# EEZ_DIB_BP3C_r2B2.net
KiCad netlist of a schematic drawn in EAGLE
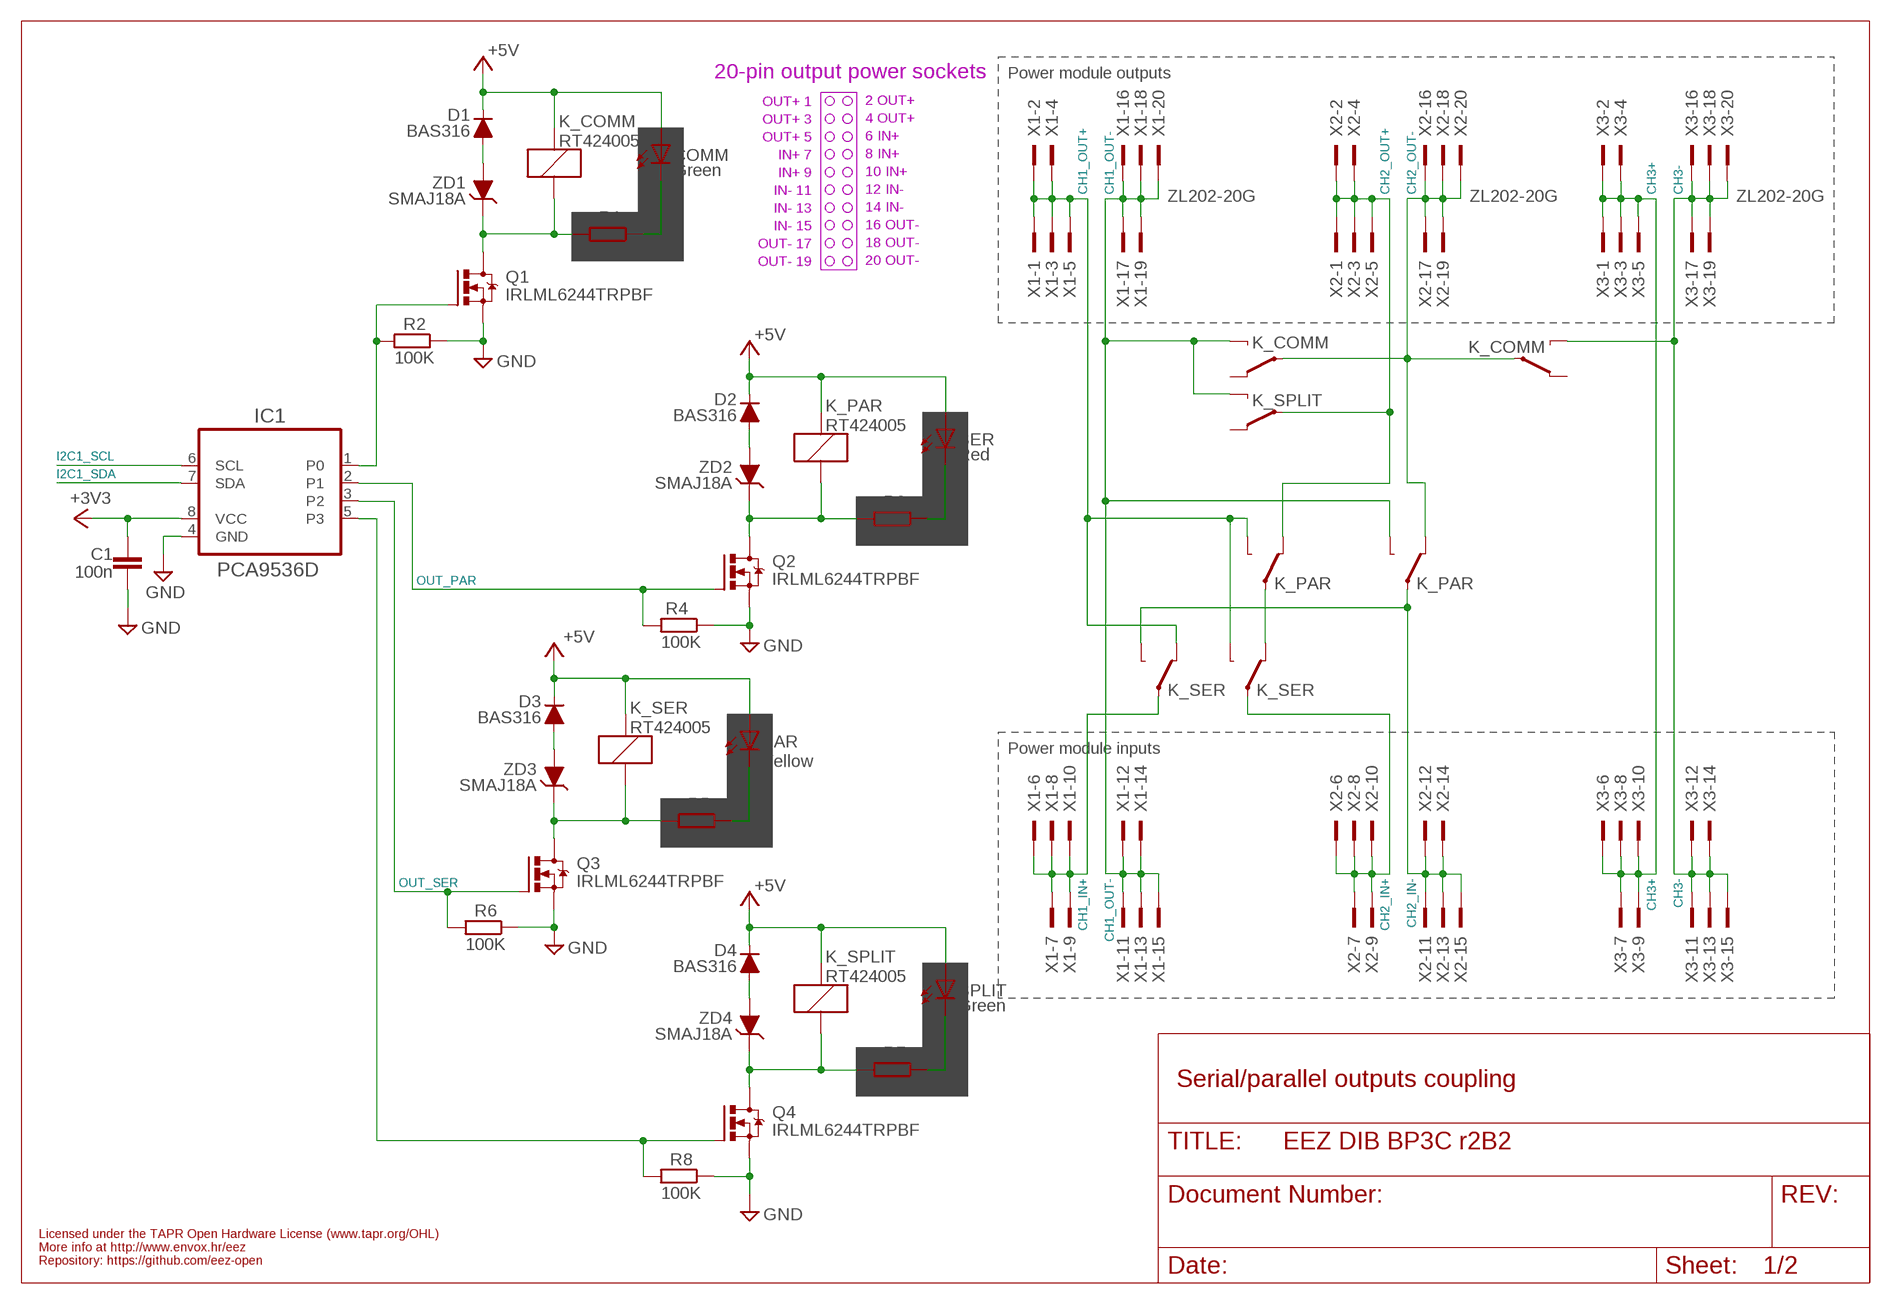
[diagram p0: schematic, sheet 1]
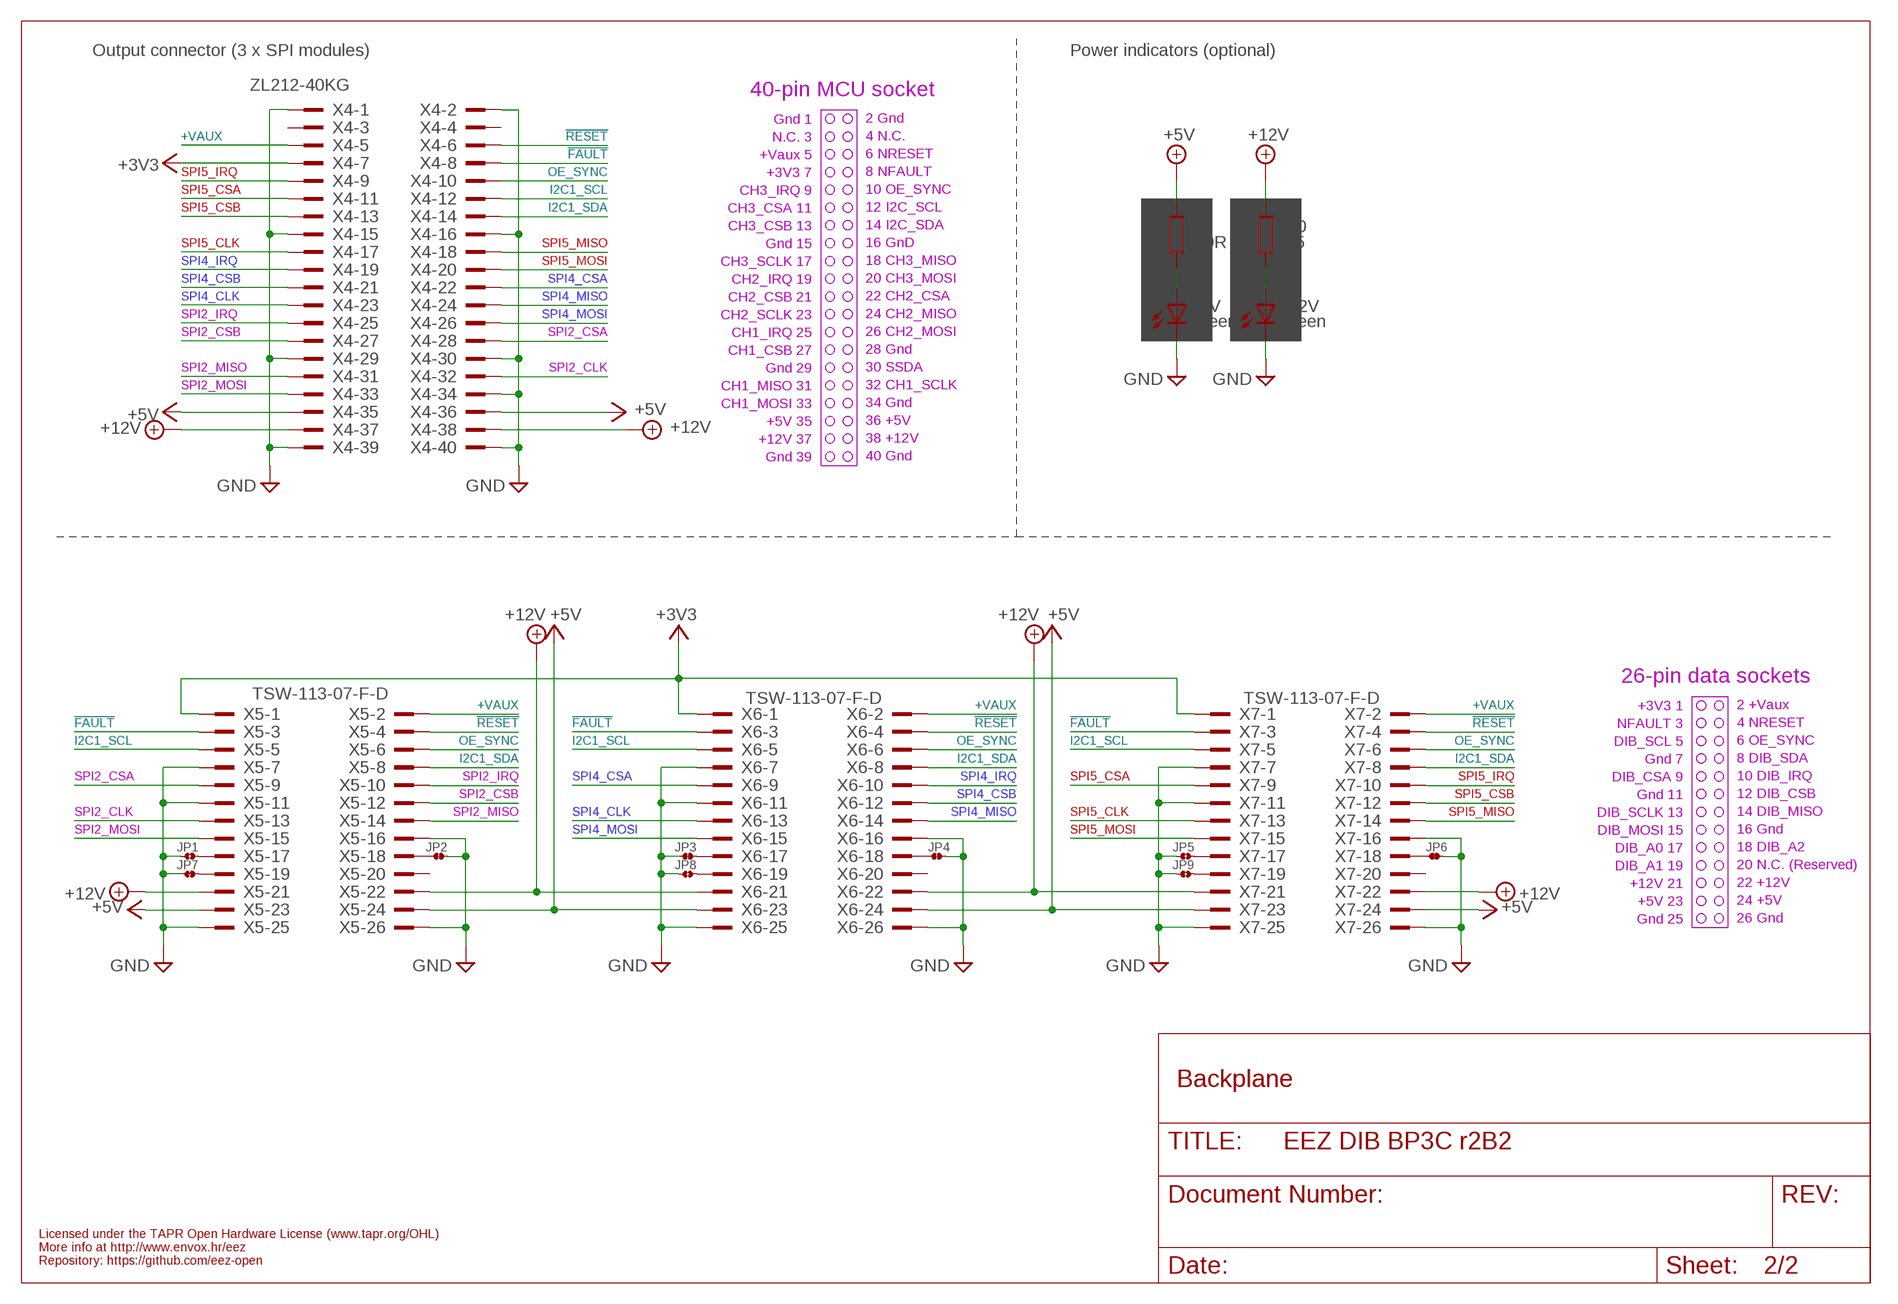
[diagram p1: schematic, sheet 2]

(export (version "E")
  (design (tool "Eeschema 10.0.6"))
  (components
    (comp (ref "C1")
      (value "100n")
      (footprint "eagle-import:C0603")
      (libsource (lib "eagle-import") (part "C-EUC0603"))
    )
    (comp (ref "COMM")
      (value "Green")
      (footprint "eagle-import:LED_0805")
      (libsource (lib "eagle-import") (part "LED0805"))
    )
    (comp (ref "D1")
      (value "BAS316")
      (footprint "eagle-import:SOD323-R")
      (libsource (lib "eagle-import") (part "DIODESOD323R"))
    )
    (comp (ref "D2")
      (value "BAS316")
      (footprint "eagle-import:SOD323-R")
      (libsource (lib "eagle-import") (part "DIODESOD323R"))
    )
    (comp (ref "D3")
      (value "BAS316")
      (footprint "eagle-import:SOD323-R")
      (libsource (lib "eagle-import") (part "DIODESOD323R"))
    )
    (comp (ref "D4")
      (value "BAS316")
      (footprint "eagle-import:SOD323-R")
      (libsource (lib "eagle-import") (part "DIODESOD323R"))
    )
    (comp (ref "IC1")
      (value "PCA9536D")
      (footprint "eagle-import:SOIC127P600X173-8N")
      (libsource (lib "eagle-import") (part "PCA9536D"))
    )
    (comp (ref "K_COMM")
      (value "RT424005")
      (footprint "eagle-import:RT-C_016A5_ROUND")
      (libsource (lib "eagle-import") (part "RELAY_RT314012-2"))
    )
    (comp (ref "K_PAR")
      (value "RT424005")
      (footprint "eagle-import:RT-C_016A5_ROUND")
      (libsource (lib "eagle-import") (part "RELAY_RT314012-2"))
    )
    (comp (ref "K_SER")
      (value "RT424005")
      (footprint "eagle-import:RT-C_016A5_ROUND")
      (libsource (lib "eagle-import") (part "RELAY_RT314012-2"))
    )
    (comp (ref "K_SPLIT")
      (value "RT424005")
      (footprint "eagle-import:RT-C_016A5_ROUND")
      (libsource (lib "eagle-import") (part "RELAY_RT314012-2"))
    )
    (comp (ref "PAR")
      (value "Yellow")
      (footprint "eagle-import:LED_0805")
      (libsource (lib "eagle-import") (part "LED0805"))
    )
    (comp (ref "Q1")
      (value "IRLML6244TRPBF")
      (footprint "eagle-import:SOT103P240X110-3N")
      (fields
        (field (name "MPN") "2N7002-7-F")
        (field (name "MPN_1") "2N7002-7-F")
        (field (name "OC_FARNELL") "1713823")
        (field (name "OC_NEWARK") "25R5679")
        (field (name "PACKAGE") "SOT-23-3")
        (field (name "SUPPLIER") "DIODES INC.")
      )
      (libsource (lib "eagle-import") (part "2N7002"))
    )
    (comp (ref "Q2")
      (value "IRLML6244TRPBF")
      (footprint "eagle-import:SOT103P240X110-3N")
      (fields
        (field (name "MPN") "2N7002-7-F")
        (field (name "MPN_1") "2N7002-7-F")
        (field (name "OC_FARNELL") "1713823")
        (field (name "OC_NEWARK") "25R5679")
        (field (name "PACKAGE") "SOT-23-3")
        (field (name "SUPPLIER") "DIODES INC.")
      )
      (libsource (lib "eagle-import") (part "2N7002"))
    )
    (comp (ref "Q3")
      (value "IRLML6244TRPBF")
      (footprint "eagle-import:SOT103P240X110-3N")
      (fields
        (field (name "MPN") "2N7002-7-F")
        (field (name "MPN_1") "2N7002-7-F")
        (field (name "OC_FARNELL") "1713823")
        (field (name "OC_NEWARK") "25R5679")
        (field (name "PACKAGE") "SOT-23-3")
        (field (name "SUPPLIER") "DIODES INC.")
      )
      (libsource (lib "eagle-import") (part "2N7002"))
    )
    (comp (ref "Q4")
      (value "IRLML6244TRPBF")
      (footprint "eagle-import:SOT103P240X110-3N")
      (fields
        (field (name "MPN") "2N7002-7-F")
        (field (name "MPN_1") "2N7002-7-F")
        (field (name "OC_FARNELL") "1713823")
        (field (name "OC_NEWARK") "25R5679")
        (field (name "PACKAGE") "SOT-23-3")
        (field (name "SUPPLIER") "DIODES INC.")
      )
      (libsource (lib "eagle-import") (part "2N7002"))
    )
    (comp (ref "R1")
      (value "330R")
      (footprint "eagle-import:R0805")
      (libsource (lib "eagle-import") (part "R-EU_R0805"))
    )
    (comp (ref "R2")
      (value "100K")
      (footprint "eagle-import:R0805")
      (libsource (lib "eagle-import") (part "R-EU_R0805"))
    )
    (comp (ref "R3")
      (value "330R")
      (footprint "eagle-import:R0805")
      (libsource (lib "eagle-import") (part "R-EU_R0805"))
    )
    (comp (ref "R4")
      (value "100K")
      (footprint "eagle-import:R0805")
      (libsource (lib "eagle-import") (part "R-EU_R0805"))
    )
    (comp (ref "R5")
      (value "330R")
      (footprint "eagle-import:R0805")
      (libsource (lib "eagle-import") (part "R-EU_R0805"))
    )
    (comp (ref "R6")
      (value "100K")
      (footprint "eagle-import:R0805")
      (libsource (lib "eagle-import") (part "R-EU_R0805"))
    )
    (comp (ref "R7")
      (value "330R")
      (footprint "eagle-import:R0805")
      (libsource (lib "eagle-import") (part "R-EU_R0805"))
    )
    (comp (ref "R8")
      (value "100K")
      (footprint "eagle-import:R0805")
      (libsource (lib "eagle-import") (part "R-EU_R0805"))
    )
    (comp (ref "SER")
      (value "Red")
      (footprint "eagle-import:LED_0805")
      (libsource (lib "eagle-import") (part "LED0805"))
    )
    (comp (ref "SPLIT")
      (value "Green")
      (footprint "eagle-import:LED_0805")
      (libsource (lib "eagle-import") (part "LED0805"))
    )
    (comp (ref "X1")
      (value "ZL202-20G")
      (footprint "eagle-import:DS1021-2_10SF11")
      (libsource (lib "eagle-import") (part "DS1021-210SF11"))
    )
    (comp (ref "X2")
      (value "ZL202-20G")
      (footprint "eagle-import:DS1021-2_10SF11")
      (libsource (lib "eagle-import") (part "DS1021-210SF11"))
    )
    (comp (ref "X3")
      (value "ZL202-20G")
      (footprint "eagle-import:DS1021-2_10SF11")
      (libsource (lib "eagle-import") (part "DS1021-210SF11"))
    )
    (comp (ref "ZD1")
      (value "SMAJ18A")
      (footprint "eagle-import:DO214AC")
      (libsource (lib "eagle-import") (part "PSMAXX"))
    )
    (comp (ref "ZD2")
      (value "SMAJ18A")
      (footprint "eagle-import:DO214AC")
      (libsource (lib "eagle-import") (part "PSMAXX"))
    )
    (comp (ref "ZD3")
      (value "SMAJ18A")
      (footprint "eagle-import:DO214AC")
      (libsource (lib "eagle-import") (part "PSMAXX"))
    )
    (comp (ref "ZD4")
      (value "SMAJ18A")
      (footprint "eagle-import:DO214AC")
      (libsource (lib "eagle-import") (part "PSMAXX"))
    )
    (comp (ref "+5V")
      (value "Green")
      (footprint "eagle-import:LED_0805")
      (libsource (lib "eagle-import") (part "LED0805"))
    )
    (comp (ref "+12V")
      (value "Green")
      (footprint "eagle-import:LED_0805")
      (libsource (lib "eagle-import") (part "LED0805"))
    )
    (comp (ref "JP1")
      (value "JP2-CUT")
      (footprint "eagle-import:JP2-CUT")
      (libsource (lib "eagle-import") (part "JP2-CUT"))
    )
    (comp (ref "JP2")
      (value "JP2-NOCUT")
      (footprint "eagle-import:JP2-NOCUT")
      (libsource (lib "eagle-import") (part "JP2-NOCUT"))
    )
    (comp (ref "JP3")
      (value "JP2-NOCUT")
      (footprint "eagle-import:JP2-NOCUT")
      (libsource (lib "eagle-import") (part "JP2-NOCUT"))
    )
    (comp (ref "JP4")
      (value "JP2-NOCUT")
      (footprint "eagle-import:JP2-NOCUT")
      (libsource (lib "eagle-import") (part "JP2-NOCUT"))
    )
    (comp (ref "JP5")
      (value "JP2-CUT")
      (footprint "eagle-import:JP2-CUT")
      (libsource (lib "eagle-import") (part "JP2-CUT"))
    )
    (comp (ref "JP6")
      (value "JP2-NOCUT")
      (footprint "eagle-import:JP2-NOCUT")
      (libsource (lib "eagle-import") (part "JP2-NOCUT"))
    )
    (comp (ref "JP7")
      (value "JP2-NOCUT")
      (footprint "eagle-import:JP2-NOCUT")
      (libsource (lib "eagle-import") (part "JP2-NOCUT"))
    )
    (comp (ref "JP8")
      (value "JP2-CUT")
      (footprint "eagle-import:JP2-CUT")
      (libsource (lib "eagle-import") (part "JP2-CUT"))
    )
    (comp (ref "JP9")
      (value "JP2-CUT")
      (footprint "eagle-import:JP2-CUT")
      (libsource (lib "eagle-import") (part "JP2-CUT"))
    )
    (comp (ref "R9")
      (value "470R")
      (footprint "eagle-import:R0805")
      (libsource (lib "eagle-import") (part "R-EU_R0805"))
    )
    (comp (ref "R10")
      (value "1K5")
      (footprint "eagle-import:R0805")
      (libsource (lib "eagle-import") (part "R-EU_R0805"))
    )
    (comp (ref "X4")
      (value "ZL212-40KG")
      (footprint "eagle-import:ZL212-40KG")
      (libsource (lib "eagle-import") (part "ZL212-40KG"))
    )
    (comp (ref "X5")
      (value "TSW-113-07-F-D")
      (footprint "eagle-import:TSW-113-07-F-D")
      (libsource (lib "eagle-import") (part "TSW-113-07-F-D"))
    )
    (comp (ref "X6")
      (value "TSW-113-07-F-D")
      (footprint "eagle-import:TSW-113-07-F-D")
      (libsource (lib "eagle-import") (part "TSW-113-07-F-D"))
    )
    (comp (ref "X7")
      (value "TSW-113-07-F-D")
      (footprint "eagle-import:TSW-113-07-F-D")
      (libsource (lib "eagle-import") (part "TSW-113-07-F-D"))
    )
  )
  (nets
    (net (code "1") (name "+3V3") (class "Default")
      (node (ref "C1") (pin "1") (pinfunction "1_1") (pintype "passive"))
      (node (ref "IC1") (pin "8") (pinfunction "VCC_8") (pintype "passive"))
      (node (ref "X4") (pin "7") (pinfunction "1_7") (pintype "passive"))
      (node (ref "X5") (pin "1") (pinfunction "1_1") (pintype "passive"))
      (node (ref "X6") (pin "1") (pinfunction "1_1") (pintype "passive"))
      (node (ref "X7") (pin "1") (pinfunction "1_1") (pintype "passive"))
    )
    (net (code "2") (name "+5V") (class "Default")
      (node (ref "COMM") (pin "A") (pinfunction "A_A") (pintype "passive"))
      (node (ref "D1") (pin "C") (pinfunction "C_C") (pintype "passive"))
      (node (ref "D2") (pin "C") (pinfunction "C_C") (pintype "passive"))
      (node (ref "D3") (pin "C") (pinfunction "C_C") (pintype "passive"))
      (node (ref "D4") (pin "C") (pinfunction "C_C") (pintype "passive"))
      (node (ref "K_COMM") (pin "A2") (pinfunction "C1_A2") (pintype "passive"))
      (node (ref "K_PAR") (pin "A2") (pinfunction "C1_A2") (pintype "passive"))
      (node (ref "K_SER") (pin "A2") (pinfunction "C1_A2") (pintype "passive"))
      (node (ref "K_SPLIT") (pin "A2") (pinfunction "C1_A2") (pintype "passive"))
      (node (ref "PAR") (pin "A") (pinfunction "A_A") (pintype "passive"))
      (node (ref "R9") (pin "1") (pinfunction "1_1") (pintype "passive"))
      (node (ref "SER") (pin "A") (pinfunction "A_A") (pintype "passive"))
      (node (ref "SPLIT") (pin "A") (pinfunction "A_A") (pintype "passive"))
      (node (ref "X4") (pin "35") (pinfunction "1_35") (pintype "passive"))
      (node (ref "X4") (pin "36") (pinfunction "1_36") (pintype "passive"))
      (node (ref "X5") (pin "23") (pinfunction "1_23") (pintype "passive"))
      (node (ref "X5") (pin "24") (pinfunction "1_24") (pintype "passive"))
      (node (ref "X6") (pin "23") (pinfunction "1_23") (pintype "passive"))
      (node (ref "X6") (pin "24") (pinfunction "1_24") (pintype "passive"))
      (node (ref "X7") (pin "23") (pinfunction "1_23") (pintype "passive"))
      (node (ref "X7") (pin "24") (pinfunction "1_24") (pintype "passive"))
    )
    (net (code "3") (name "+12V") (class "Default")
      (node (ref "R10") (pin "1") (pinfunction "1_1") (pintype "passive"))
      (node (ref "X4") (pin "37") (pinfunction "1_37") (pintype "passive"))
      (node (ref "X4") (pin "38") (pinfunction "1_38") (pintype "passive"))
      (node (ref "X5") (pin "21") (pinfunction "1_21") (pintype "passive"))
      (node (ref "X5") (pin "22") (pinfunction "1_22") (pintype "passive"))
      (node (ref "X6") (pin "21") (pinfunction "1_21") (pintype "passive"))
      (node (ref "X6") (pin "22") (pinfunction "1_22") (pintype "passive"))
      (node (ref "X7") (pin "21") (pinfunction "1_21") (pintype "passive"))
      (node (ref "X7") (pin "22") (pinfunction "1_22") (pintype "passive"))
    )
    (net (code "4") (name "+VAUX") (class "Default")
      (node (ref "X4") (pin "5") (pinfunction "1_5") (pintype "passive"))
      (node (ref "X5") (pin "2") (pinfunction "1_2") (pintype "passive"))
      (node (ref "X6") (pin "2") (pinfunction "1_2") (pintype "passive"))
      (node (ref "X7") (pin "2") (pinfunction "1_2") (pintype "passive"))
    )
    (net (code "5") (name "CH1_IN+") (class "Default")
      (node (ref "K_SER") (pin "11A") (pinfunction "P_11A") (pintype "passive"))
      (node (ref "X1") (pin "10") (pinfunction "1_10") (pintype "passive"))
      (node (ref "X1") (pin "6") (pinfunction "1_6") (pintype "passive"))
      (node (ref "X1") (pin "7") (pinfunction "1_7") (pintype "passive"))
      (node (ref "X1") (pin "8") (pinfunction "1_8") (pintype "passive"))
      (node (ref "X1") (pin "9") (pinfunction "1_9") (pintype "passive"))
    )
    (net (code "6") (name "CH1_OUT+") (class "Default")
      (node (ref "K_PAR") (pin "14A") (pinfunction "O_14A") (pintype "passive"))
      (node (ref "K_SER") (pin "12A") (pinfunction "S_12A") (pintype "passive"))
      (node (ref "K_SER") (pin "14B") (pinfunction "O_14B") (pintype "passive"))
      (node (ref "X1") (pin "1") (pinfunction "1_1") (pintype "passive"))
      (node (ref "X1") (pin "2") (pinfunction "1_2") (pintype "passive"))
      (node (ref "X1") (pin "3") (pinfunction "1_3") (pintype "passive"))
      (node (ref "X1") (pin "4") (pinfunction "1_4") (pintype "passive"))
      (node (ref "X1") (pin "5") (pinfunction "1_5") (pintype "passive"))
    )
    (net (code "7") (name "CH1_OUT-") (class "Default")
      (node (ref "K_COMM") (pin "14A") (pinfunction "O_14A") (pintype "passive"))
      (node (ref "K_PAR") (pin "14B") (pinfunction "O_14B") (pintype "passive"))
      (node (ref "K_SPLIT") (pin "14A") (pinfunction "O_14A") (pintype "passive"))
      (node (ref "X1") (pin "11") (pinfunction "1_11") (pintype "passive"))
      (node (ref "X1") (pin "12") (pinfunction "1_12") (pintype "passive"))
      (node (ref "X1") (pin "13") (pinfunction "1_13") (pintype "passive"))
      (node (ref "X1") (pin "14") (pinfunction "1_14") (pintype "passive"))
      (node (ref "X1") (pin "15") (pinfunction "1_15") (pintype "passive"))
      (node (ref "X1") (pin "16") (pinfunction "1_16") (pintype "passive"))
      (node (ref "X1") (pin "17") (pinfunction "1_17") (pintype "passive"))
      (node (ref "X1") (pin "18") (pinfunction "1_18") (pintype "passive"))
      (node (ref "X1") (pin "19") (pinfunction "1_19") (pintype "passive"))
      (node (ref "X1") (pin "20") (pinfunction "1_20") (pintype "passive"))
    )
    (net (code "8") (name "CH2_IN+") (class "Default")
      (node (ref "K_SER") (pin "11B") (pinfunction "P_11B") (pintype "passive"))
      (node (ref "X2") (pin "10") (pinfunction "1_10") (pintype "passive"))
      (node (ref "X2") (pin "6") (pinfunction "1_6") (pintype "passive"))
      (node (ref "X2") (pin "7") (pinfunction "1_7") (pintype "passive"))
      (node (ref "X2") (pin "8") (pinfunction "1_8") (pintype "passive"))
      (node (ref "X2") (pin "9") (pinfunction "1_9") (pintype "passive"))
    )
    (net (code "9") (name "CH2_IN-") (class "Default")
      (node (ref "K_PAR") (pin "11B") (pinfunction "P_11B") (pintype "passive"))
      (node (ref "K_SER") (pin "14A") (pinfunction "O_14A") (pintype "passive"))
      (node (ref "X2") (pin "11") (pinfunction "1_11") (pintype "passive"))
      (node (ref "X2") (pin "12") (pinfunction "1_12") (pintype "passive"))
      (node (ref "X2") (pin "13") (pinfunction "1_13") (pintype "passive"))
      (node (ref "X2") (pin "14") (pinfunction "1_14") (pintype "passive"))
      (node (ref "X2") (pin "15") (pinfunction "1_15") (pintype "passive"))
    )
    (net (code "10") (name "CH2_OUT+") (class "Default")
      (node (ref "K_PAR") (pin "12A") (pinfunction "S_12A") (pintype "passive"))
      (node (ref "K_SPLIT") (pin "11A") (pinfunction "P_11A") (pintype "passive"))
      (node (ref "X2") (pin "1") (pinfunction "1_1") (pintype "passive"))
      (node (ref "X2") (pin "2") (pinfunction "1_2") (pintype "passive"))
      (node (ref "X2") (pin "3") (pinfunction "1_3") (pintype "passive"))
      (node (ref "X2") (pin "4") (pinfunction "1_4") (pintype "passive"))
      (node (ref "X2") (pin "5") (pinfunction "1_5") (pintype "passive"))
    )
    (net (code "11") (name "CH2_OUT-") (class "Default")
      (node (ref "K_COMM") (pin "11A") (pinfunction "P_11A") (pintype "passive"))
      (node (ref "K_COMM") (pin "11B") (pinfunction "P_11B") (pintype "passive"))
      (node (ref "K_PAR") (pin "12B") (pinfunction "S_12B") (pintype "passive"))
      (node (ref "X2") (pin "16") (pinfunction "1_16") (pintype "passive"))
      (node (ref "X2") (pin "17") (pinfunction "1_17") (pintype "passive"))
      (node (ref "X2") (pin "18") (pinfunction "1_18") (pintype "passive"))
      (node (ref "X2") (pin "19") (pinfunction "1_19") (pintype "passive"))
      (node (ref "X2") (pin "20") (pinfunction "1_20") (pintype "passive"))
    )
    (net (code "12") (name "CH3+") (class "Default")
      (node (ref "X3") (pin "1") (pinfunction "1_1") (pintype "passive"))
      (node (ref "X3") (pin "10") (pinfunction "1_10") (pintype "passive"))
      (node (ref "X3") (pin "2") (pinfunction "1_2") (pintype "passive"))
      (node (ref "X3") (pin "3") (pinfunction "1_3") (pintype "passive"))
      (node (ref "X3") (pin "4") (pinfunction "1_4") (pintype "passive"))
      (node (ref "X3") (pin "5") (pinfunction "1_5") (pintype "passive"))
      (node (ref "X3") (pin "6") (pinfunction "1_6") (pintype "passive"))
      (node (ref "X3") (pin "7") (pinfunction "1_7") (pintype "passive"))
      (node (ref "X3") (pin "8") (pinfunction "1_8") (pintype "passive"))
      (node (ref "X3") (pin "9") (pinfunction "1_9") (pintype "passive"))
    )
    (net (code "13") (name "CH3-") (class "Default")
      (node (ref "K_COMM") (pin "14B") (pinfunction "O_14B") (pintype "passive"))
      (node (ref "X3") (pin "11") (pinfunction "1_11") (pintype "passive"))
      (node (ref "X3") (pin "12") (pinfunction "1_12") (pintype "passive"))
      (node (ref "X3") (pin "13") (pinfunction "1_13") (pintype "passive"))
      (node (ref "X3") (pin "14") (pinfunction "1_14") (pintype "passive"))
      (node (ref "X3") (pin "15") (pinfunction "1_15") (pintype "passive"))
      (node (ref "X3") (pin "16") (pinfunction "1_16") (pintype "passive"))
      (node (ref "X3") (pin "17") (pinfunction "1_17") (pintype "passive"))
      (node (ref "X3") (pin "18") (pinfunction "1_18") (pintype "passive"))
      (node (ref "X3") (pin "19") (pinfunction "1_19") (pintype "passive"))
      (node (ref "X3") (pin "20") (pinfunction "1_20") (pintype "passive"))
    )
    (net (code "14") (name "GND") (class "Default")
      (node (ref "+12V") (pin "C") (pinfunction "C_C") (pintype "passive"))
      (node (ref "+5V") (pin "C") (pinfunction "C_C") (pintype "passive"))
      (node (ref "C1") (pin "2") (pinfunction "2_2") (pintype "passive"))
      (node (ref "IC1") (pin "4") (pinfunction "GND_4") (pintype "passive"))
      (node (ref "JP1") (pin "1") (pinfunction "1_1") (pintype "passive"))
      (node (ref "JP2") (pin "2") (pinfunction "2_2") (pintype "passive"))
      (node (ref "JP3") (pin "1") (pinfunction "1_1") (pintype "passive"))
      (node (ref "JP4") (pin "2") (pinfunction "2_2") (pintype "passive"))
      (node (ref "JP5") (pin "1") (pinfunction "1_1") (pintype "passive"))
      (node (ref "JP6") (pin "2") (pinfunction "2_2") (pintype "passive"))
      (node (ref "JP7") (pin "1") (pinfunction "1_1") (pintype "passive"))
      (node (ref "JP8") (pin "1") (pinfunction "1_1") (pintype "passive"))
      (node (ref "JP9") (pin "1") (pinfunction "1_1") (pintype "passive"))
      (node (ref "Q1") (pin "2") (pinfunction "S_2") (pintype "passive"))
      (node (ref "Q2") (pin "2") (pinfunction "S_2") (pintype "passive"))
      (node (ref "Q3") (pin "2") (pinfunction "S_2") (pintype "passive"))
      (node (ref "Q4") (pin "2") (pinfunction "S_2") (pintype "passive"))
      (node (ref "R2") (pin "1") (pinfunction "1_1") (pintype "passive"))
      (node (ref "R4") (pin "1") (pinfunction "1_1") (pintype "passive"))
      (node (ref "R6") (pin "1") (pinfunction "1_1") (pintype "passive"))
      (node (ref "R8") (pin "1") (pinfunction "1_1") (pintype "passive"))
      (node (ref "X4") (pin "1") (pinfunction "1_1") (pintype "passive"))
      (node (ref "X4") (pin "15") (pinfunction "1_15") (pintype "passive"))
      (node (ref "X4") (pin "16") (pinfunction "1_16") (pintype "passive"))
      (node (ref "X4") (pin "2") (pinfunction "1_2") (pintype "passive"))
      (node (ref "X4") (pin "29") (pinfunction "1_29") (pintype "passive"))
      (node (ref "X4") (pin "30") (pinfunction "1_30") (pintype "passive"))
      (node (ref "X4") (pin "34") (pinfunction "1_34") (pintype "passive"))
      (node (ref "X4") (pin "39") (pinfunction "1_39") (pintype "passive"))
      (node (ref "X4") (pin "40") (pinfunction "1_40") (pintype "passive"))
      (node (ref "X5") (pin "11") (pinfunction "1_11") (pintype "passive"))
      (node (ref "X5") (pin "16") (pinfunction "1_16") (pintype "passive"))
      (node (ref "X5") (pin "25") (pinfunction "1_25") (pintype "passive"))
      (node (ref "X5") (pin "26") (pinfunction "1_26") (pintype "passive"))
      (node (ref "X5") (pin "7") (pinfunction "1_7") (pintype "passive"))
      (node (ref "X6") (pin "11") (pinfunction "1_11") (pintype "passive"))
      (node (ref "X6") (pin "16") (pinfunction "1_16") (pintype "passive"))
      (node (ref "X6") (pin "25") (pinfunction "1_25") (pintype "passive"))
      (node (ref "X6") (pin "26") (pinfunction "1_26") (pintype "passive"))
      (node (ref "X6") (pin "7") (pinfunction "1_7") (pintype "passive"))
      (node (ref "X7") (pin "11") (pinfunction "1_11") (pintype "passive"))
      (node (ref "X7") (pin "16") (pinfunction "1_16") (pintype "passive"))
      (node (ref "X7") (pin "25") (pinfunction "1_25") (pintype "passive"))
      (node (ref "X7") (pin "26") (pinfunction "1_26") (pintype "passive"))
      (node (ref "X7") (pin "7") (pinfunction "1_7") (pintype "passive"))
    )
    (net (code "15") (name "I2C1_SCL") (class "Default")
      (node (ref "IC1") (pin "6") (pinfunction "SCL_6") (pintype "input"))
      (node (ref "X4") (pin "12") (pinfunction "1_12") (pintype "passive"))
      (node (ref "X5") (pin "5") (pinfunction "1_5") (pintype "passive"))
      (node (ref "X6") (pin "5") (pinfunction "1_5") (pintype "passive"))
      (node (ref "X7") (pin "5") (pinfunction "1_5") (pintype "passive"))
    )
    (net (code "16") (name "I2C1_SDA") (class "Default")
      (node (ref "IC1") (pin "7") (pinfunction "SDA_7") (pintype "bidirectional"))
      (node (ref "X4") (pin "14") (pinfunction "1_14") (pintype "passive"))
      (node (ref "X5") (pin "8") (pinfunction "1_8") (pintype "passive"))
      (node (ref "X6") (pin "8") (pinfunction "1_8") (pintype "passive"))
      (node (ref "X7") (pin "8") (pinfunction "1_8") (pintype "passive"))
    )
    (net (code "17") (name "Net-(+5V-PadA)") (class "Default")
      (node (ref "+5V") (pin "A") (pinfunction "A_A") (pintype "passive"))
      (node (ref "R9") (pin "2") (pinfunction "2_2") (pintype "passive"))
    )
    (net (code "18") (name "Net-(+12V-PadA)") (class "Default")
      (node (ref "+12V") (pin "A") (pinfunction "A_A") (pintype "passive"))
      (node (ref "R10") (pin "2") (pinfunction "2_2") (pintype "passive"))
    )
    (net (code "19") (name "Net-(COMM-PadC)") (class "Default")
      (node (ref "COMM") (pin "C") (pinfunction "C_C") (pintype "passive"))
      (node (ref "R1") (pin "1") (pinfunction "1_1") (pintype "passive"))
    )
    (net (code "20") (name "Net-(D1-PadA)") (class "Default")
      (node (ref "D1") (pin "A") (pinfunction "A_A") (pintype "passive"))
      (node (ref "ZD1") (pin "A") (pinfunction "A_A") (pintype "passive"))
    )
    (net (code "21") (name "Net-(D2-PadA)") (class "Default")
      (node (ref "D2") (pin "A") (pinfunction "A_A") (pintype "passive"))
      (node (ref "ZD2") (pin "A") (pinfunction "A_A") (pintype "passive"))
    )
    (net (code "22") (name "Net-(D3-PadA)") (class "Default")
      (node (ref "D3") (pin "A") (pinfunction "A_A") (pintype "passive"))
      (node (ref "ZD3") (pin "A") (pinfunction "A_A") (pintype "passive"))
    )
    (net (code "23") (name "Net-(D4-PadA)") (class "Default")
      (node (ref "D4") (pin "A") (pinfunction "A_A") (pintype "passive"))
      (node (ref "ZD4") (pin "A") (pinfunction "A_A") (pintype "passive"))
    )
    (net (code "24") (name "Net-(IC1-P0)") (class "Default")
      (node (ref "IC1") (pin "1") (pinfunction "P0_1") (pintype "bidirectional"))
      (node (ref "Q1") (pin "1") (pinfunction "G_1") (pintype "passive"))
      (node (ref "R2") (pin "2") (pinfunction "2_2") (pintype "passive"))
    )
    (net (code "25") (name "Net-(IC1-P3)") (class "Default")
      (node (ref "IC1") (pin "5") (pinfunction "P3_5") (pintype "bidirectional"))
      (node (ref "Q4") (pin "1") (pinfunction "G_1") (pintype "passive"))
      (node (ref "R8") (pin "2") (pinfunction "2_2") (pintype "passive"))
    )
    (net (code "26") (name "Net-(K_COMMC-C2)") (class "Default")
      (node (ref "K_COMM") (pin "A1") (pinfunction "C2_A1") (pintype "passive"))
      (node (ref "Q1") (pin "3") (pinfunction "D_3") (pintype "passive"))
      (node (ref "R1") (pin "2") (pinfunction "2_2") (pintype "passive"))
      (node (ref "ZD1") (pin "C") (pinfunction "C_C") (pintype "passive"))
    )
    (net (code "27") (name "Net-(K_PARA-P)") (class "Default")
      (node (ref "K_PAR") (pin "11A") (pinfunction "P_11A") (pintype "passive"))
      (node (ref "K_SER") (pin "12B") (pinfunction "S_12B") (pintype "passive"))
    )
    (net (code "28") (name "Net-(K_PARC-C2)") (class "Default")
      (node (ref "K_PAR") (pin "A1") (pinfunction "C2_A1") (pintype "passive"))
      (node (ref "Q2") (pin "3") (pinfunction "D_3") (pintype "passive"))
      (node (ref "R3") (pin "2") (pinfunction "2_2") (pintype "passive"))
      (node (ref "ZD2") (pin "C") (pinfunction "C_C") (pintype "passive"))
    )
    (net (code "29") (name "Net-(K_SERC-C2)") (class "Default")
      (node (ref "K_SER") (pin "A1") (pinfunction "C2_A1") (pintype "passive"))
      (node (ref "Q3") (pin "3") (pinfunction "D_3") (pintype "passive"))
      (node (ref "R5") (pin "2") (pinfunction "2_2") (pintype "passive"))
      (node (ref "ZD3") (pin "C") (pinfunction "C_C") (pintype "passive"))
    )
    (net (code "30") (name "Net-(K_SPLITC-C2)") (class "Default")
      (node (ref "K_SPLIT") (pin "A1") (pinfunction "C2_A1") (pintype "passive"))
      (node (ref "Q4") (pin "3") (pinfunction "D_3") (pintype "passive"))
      (node (ref "R7") (pin "2") (pinfunction "2_2") (pintype "passive"))
      (node (ref "ZD4") (pin "C") (pinfunction "C_C") (pintype "passive"))
    )
    (net (code "31") (name "Net-(PAR-PadC)") (class "Default")
      (node (ref "PAR") (pin "C") (pinfunction "C_C") (pintype "passive"))
      (node (ref "R5") (pin "1") (pinfunction "1_1") (pintype "passive"))
    )
    (net (code "32") (name "Net-(R3-Pad1)") (class "Default")
      (node (ref "R3") (pin "1") (pinfunction "1_1") (pintype "passive"))
      (node (ref "SER") (pin "C") (pinfunction "C_C") (pintype "passive"))
    )
    (net (code "33") (name "Net-(R7-Pad1)") (class "Default")
      (node (ref "R7") (pin "1") (pinfunction "1_1") (pintype "passive"))
      (node (ref "SPLIT") (pin "C") (pinfunction "C_C") (pintype "passive"))
    )
    (net (code "34") (name "Net-(X5I-1)") (class "Default")
      (node (ref "JP1") (pin "2") (pinfunction "2_2") (pintype "passive"))
      (node (ref "X5") (pin "17") (pinfunction "1_17") (pintype "passive"))
    )
    (net (code "35") (name "Net-(X5J-1)") (class "Default")
      (node (ref "JP2") (pin "1") (pinfunction "1_1") (pintype "passive"))
      (node (ref "X5") (pin "18") (pinfunction "1_18") (pintype "passive"))
    )
    (net (code "36") (name "Net-(X5K-1)") (class "Default")
      (node (ref "JP7") (pin "2") (pinfunction "2_2") (pintype "passive"))
      (node (ref "X5") (pin "19") (pinfunction "1_19") (pintype "passive"))
    )
    (net (code "37") (name "Net-(X6I-1)") (class "Default")
      (node (ref "JP3") (pin "2") (pinfunction "2_2") (pintype "passive"))
      (node (ref "X6") (pin "17") (pinfunction "1_17") (pintype "passive"))
    )
    (net (code "38") (name "Net-(X6J-1)") (class "Default")
      (node (ref "JP4") (pin "1") (pinfunction "1_1") (pintype "passive"))
      (node (ref "X6") (pin "18") (pinfunction "1_18") (pintype "passive"))
    )
    (net (code "39") (name "Net-(X6K-1)") (class "Default")
      (node (ref "JP8") (pin "2") (pinfunction "2_2") (pintype "passive"))
      (node (ref "X6") (pin "19") (pinfunction "1_19") (pintype "passive"))
    )
    (net (code "40") (name "Net-(X7I-1)") (class "Default")
      (node (ref "JP5") (pin "2") (pinfunction "2_2") (pintype "passive"))
      (node (ref "X7") (pin "17") (pinfunction "1_17") (pintype "passive"))
    )
    (net (code "41") (name "Net-(X7J-1)") (class "Default")
      (node (ref "JP6") (pin "1") (pinfunction "1_1") (pintype "passive"))
      (node (ref "X7") (pin "18") (pinfunction "1_18") (pintype "passive"))
    )
    (net (code "42") (name "Net-(X7K-1)") (class "Default")
      (node (ref "JP9") (pin "2") (pinfunction "2_2") (pintype "passive"))
      (node (ref "X7") (pin "19") (pinfunction "1_19") (pintype "passive"))
    )
    (net (code "43") (name "OE_SYNC") (class "Default")
      (node (ref "X4") (pin "10") (pinfunction "1_10") (pintype "passive"))
      (node (ref "X5") (pin "6") (pinfunction "1_6") (pintype "passive"))
      (node (ref "X6") (pin "6") (pinfunction "1_6") (pintype "passive"))
      (node (ref "X7") (pin "6") (pinfunction "1_6") (pintype "passive"))
    )
    (net (code "44") (name "OUT_PAR") (class "Default")
      (node (ref "IC1") (pin "2") (pinfunction "P1_2") (pintype "bidirectional"))
      (node (ref "Q2") (pin "1") (pinfunction "G_1") (pintype "passive"))
      (node (ref "R4") (pin "2") (pinfunction "2_2") (pintype "passive"))
    )
    (net (code "45") (name "OUT_SER") (class "Default")
      (node (ref "IC1") (pin "3") (pinfunction "P2_3") (pintype "bidirectional"))
      (node (ref "Q3") (pin "1") (pinfunction "G_1") (pintype "passive"))
      (node (ref "R6") (pin "2") (pinfunction "2_2") (pintype "passive"))
    )
    (net (code "46") (name "SPI2_CLK") (class "Default")
      (node (ref "X4") (pin "32") (pinfunction "1_32") (pintype "passive"))
      (node (ref "X5") (pin "13") (pinfunction "1_13") (pintype "passive"))
    )
    (net (code "47") (name "SPI2_CSA") (class "Default")
      (node (ref "X4") (pin "28") (pinfunction "1_28") (pintype "passive"))
      (node (ref "X5") (pin "9") (pinfunction "1_9") (pintype "passive"))
    )
    (net (code "48") (name "SPI2_CSB") (class "Default")
      (node (ref "X4") (pin "27") (pinfunction "1_27") (pintype "passive"))
      (node (ref "X5") (pin "12") (pinfunction "1_12") (pintype "passive"))
    )
    (net (code "49") (name "SPI2_IRQ") (class "Default")
      (node (ref "X4") (pin "25") (pinfunction "1_25") (pintype "passive"))
      (node (ref "X5") (pin "10") (pinfunction "1_10") (pintype "passive"))
    )
    (net (code "50") (name "SPI2_MISO") (class "Default")
      (node (ref "X4") (pin "31") (pinfunction "1_31") (pintype "passive"))
      (node (ref "X5") (pin "14") (pinfunction "1_14") (pintype "passive"))
    )
    (net (code "51") (name "SPI2_MOSI") (class "Default")
      (node (ref "X4") (pin "33") (pinfunction "1_33") (pintype "passive"))
      (node (ref "X5") (pin "15") (pinfunction "1_15") (pintype "passive"))
    )
    (net (code "52") (name "SPI4_CLK") (class "Default")
      (node (ref "X4") (pin "23") (pinfunction "1_23") (pintype "passive"))
      (node (ref "X6") (pin "13") (pinfunction "1_13") (pintype "passive"))
    )
    (net (code "53") (name "SPI4_CSA") (class "Default")
      (node (ref "X4") (pin "22") (pinfunction "1_22") (pintype "passive"))
      (node (ref "X6") (pin "9") (pinfunction "1_9") (pintype "passive"))
    )
    (net (code "54") (name "SPI4_CSB") (class "Default")
      (node (ref "X4") (pin "21") (pinfunction "1_21") (pintype "passive"))
      (node (ref "X6") (pin "12") (pinfunction "1_12") (pintype "passive"))
    )
    (net (code "55") (name "SPI4_IRQ") (class "Default")
      (node (ref "X4") (pin "19") (pinfunction "1_19") (pintype "passive"))
      (node (ref "X6") (pin "10") (pinfunction "1_10") (pintype "passive"))
    )
    (net (code "56") (name "SPI4_MISO") (class "Default")
      (node (ref "X4") (pin "24") (pinfunction "1_24") (pintype "passive"))
      (node (ref "X6") (pin "14") (pinfunction "1_14") (pintype "passive"))
    )
    (net (code "57") (name "SPI4_MOSI") (class "Default")
      (node (ref "X4") (pin "26") (pinfunction "1_26") (pintype "passive"))
      (node (ref "X6") (pin "15") (pinfunction "1_15") (pintype "passive"))
    )
    (net (code "58") (name "SPI5_CLK") (class "Default")
      (node (ref "X4") (pin "17") (pinfunction "1_17") (pintype "passive"))
      (node (ref "X7") (pin "13") (pinfunction "1_13") (pintype "passive"))
    )
    (net (code "59") (name "SPI5_CSA") (class "Default")
      (node (ref "X4") (pin "11") (pinfunction "1_11") (pintype "passive"))
      (node (ref "X7") (pin "9") (pinfunction "1_9") (pintype "passive"))
    )
    (net (code "60") (name "SPI5_CSB") (class "Default")
      (node (ref "X4") (pin "13") (pinfunction "1_13") (pintype "passive"))
      (node (ref "X7") (pin "12") (pinfunction "1_12") (pintype "passive"))
    )
    (net (code "61") (name "SPI5_IRQ") (class "Default")
      (node (ref "X4") (pin "9") (pinfunction "1_9") (pintype "passive"))
      (node (ref "X7") (pin "10") (pinfunction "1_10") (pintype "passive"))
    )
    (net (code "62") (name "SPI5_MISO") (class "Default")
      (node (ref "X4") (pin "18") (pinfunction "1_18") (pintype "passive"))
      (node (ref "X7") (pin "14") (pinfunction "1_14") (pintype "passive"))
    )
    (net (code "63") (name "SPI5_MOSI") (class "Default")
      (node (ref "X4") (pin "20") (pinfunction "1_20") (pintype "passive"))
      (node (ref "X7") (pin "15") (pinfunction "1_15") (pintype "passive"))
    )
    (net (code "64") (name "unconnected-(K_COMMA-S-Pad12A)") (class "Default")
      (node (ref "K_COMM") (pin "12A") (pinfunction "S_12A") (pintype "passive"))
    )
    (net (code "65") (name "unconnected-(K_COMMB-S-Pad12B)") (class "Default")
      (node (ref "K_COMM") (pin "12B") (pinfunction "S_12B") (pintype "passive"))
    )
    (net (code "66") (name "unconnected-(K_SPLITA-S-Pad12A)") (class "Default")
      (node (ref "K_SPLIT") (pin "12A") (pinfunction "S_12A") (pintype "passive"))
    )
    (net (code "67") (name "unconnected-(X4AH-1-Pad4)") (class "Default")
      (node (ref "X4") (pin "4") (pinfunction "1_4") (pintype "passive"))
    )
    (net (code "68") (name "unconnected-(X4W-1-Pad3)") (class "Default")
      (node (ref "X4") (pin "3") (pinfunction "1_3") (pintype "passive"))
    )
    (net (code "69") (name "unconnected-(X5M-1-Pad20)") (class "Default")
      (node (ref "X5") (pin "20") (pinfunction "1_20") (pintype "passive"))
    )
    (net (code "70") (name "unconnected-(X6M-1-Pad20)") (class "Default")
      (node (ref "X6") (pin "20") (pinfunction "1_20") (pintype "passive"))
    )
    (net (code "71") (name "unconnected-(X7M-1-Pad20)") (class "Default")
      (node (ref "X7") (pin "20") (pinfunction "1_20") (pintype "passive"))
    )
    (net (code "72") (name "~{FAULT}") (class "Default")
      (node (ref "X4") (pin "8") (pinfunction "1_8") (pintype "passive"))
      (node (ref "X5") (pin "3") (pinfunction "1_3") (pintype "passive"))
      (node (ref "X6") (pin "3") (pinfunction "1_3") (pintype "passive"))
      (node (ref "X7") (pin "3") (pinfunction "1_3") (pintype "passive"))
    )
    (net (code "73") (name "~{RESET}") (class "Default")
      (node (ref "X4") (pin "6") (pinfunction "1_6") (pintype "passive"))
      (node (ref "X5") (pin "4") (pinfunction "1_4") (pintype "passive"))
      (node (ref "X6") (pin "4") (pinfunction "1_4") (pintype "passive"))
      (node (ref "X7") (pin "4") (pinfunction "1_4") (pintype "passive"))
    )
  )
)
